# stm8l_resp_v2_0.net
KiCad netlist of a schematic drawn in Altium Designer
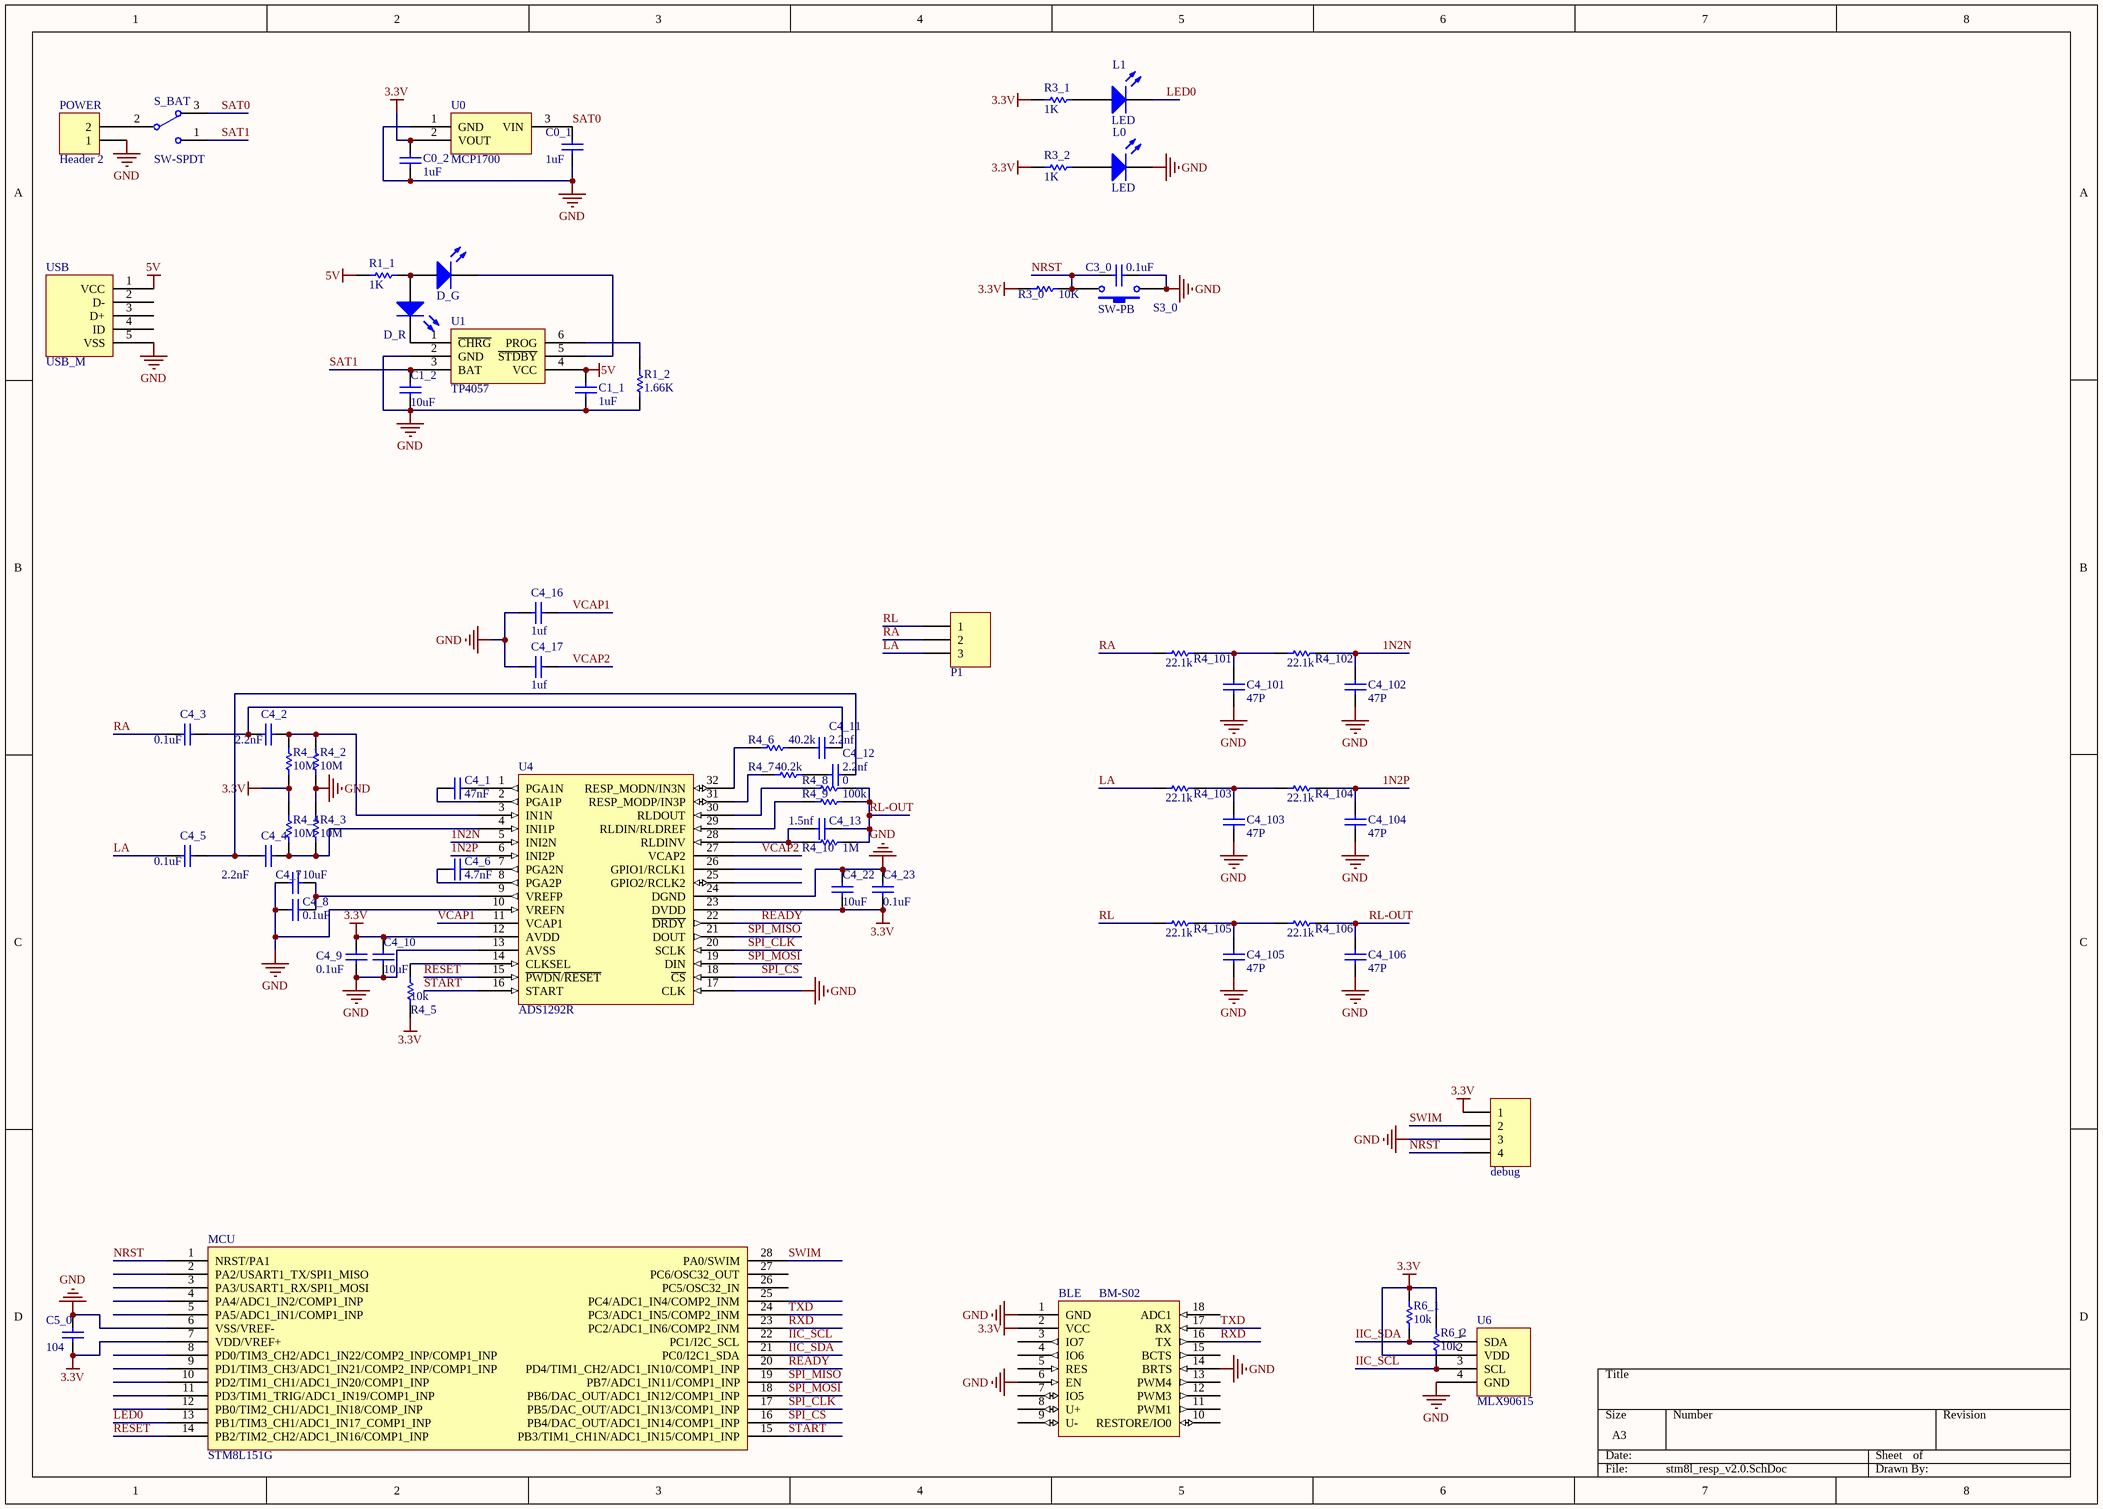
[diagram p0: stm8l_resp_v2.0.SchDoc]

(export (version "E")
  (design (tool "Eeschema 10.0.6"))
  (components
    (comp (ref "BLE")
      (value "BM-S02")
      (footprint "BM-S02")
      (description "蓝牙4.0模块")
      (libsource (lib "Devin_Lib") (part "BM-S02"))
    )
    (comp (ref "C0_1")
      (value "1uF")
      (footprint "C-RAD-0603")
      (description "无极性电容")
      (fields (field (name "Comment") "Cap") (field (name "PUBLISHER") "Altium Limited"))
      (libsource (lib "Devin_Lib") (part "Cap"))
    )
    (comp (ref "C0_2")
      (value "1uF")
      (footprint "C-RAD-0603")
      (description "无极性电容")
      (fields (field (name "Comment") "Cap") (field (name "PUBLISHER") "Altium Limited"))
      (libsource (lib "Devin_Lib") (part "Cap"))
    )
    (comp (ref "C1_1")
      (value "1uF")
      (footprint "C-RAD-0603")
      (description "无极性电容")
      (fields (field (name "Comment") "Cap") (field (name "PUBLISHER") "Altium Limited"))
      (libsource (lib "Devin_Lib") (part "Cap"))
    )
    (comp (ref "C1_2")
      (value "10uF")
      (footprint "C-RAD-0603")
      (description "无极性电容")
      (fields (field (name "Comment") "Cap") (field (name "PUBLISHER") "Altium Limited"))
      (libsource (lib "Schlib1") (part "Cap"))
    )
    (comp (ref "C3_0")
      (value "0.1uF")
      (footprint "C-RAD-0603")
      (description "无极性电容")
      (fields (field (name "Comment") "Cap") (field (name "PUBLISHER") "Altium Limited"))
      (libsource (lib "Fszhang") (part "Cap"))
    )
    (comp (ref "C4_1")
      (value "47nF")
      (footprint "C-RAD-0603")
      (description "无极性电容")
      (fields (field (name "Comment") "Cap") (field (name "PUBLISHER") "Altium Limited"))
      (libsource (lib "Schlib1") (part "Cap"))
    )
    (comp (ref "C4_2")
      (value "2.2nF")
      (footprint "C-RAD-0603")
      (description "无极性电容")
      (fields (field (name "Comment") "Cap") (field (name "PUBLISHER") "Altium Limited"))
      (libsource (lib "Schlib1") (part "Cap"))
    )
    (comp (ref "C4_3")
      (value "0.1uF")
      (footprint "C-RAD-0603")
      (description "无极性电容")
      (fields (field (name "Comment") "Cap") (field (name "PUBLISHER") "Altium Limited"))
      (libsource (lib "Schlib1") (part "Cap"))
    )
    (comp (ref "C4_4")
      (value "2.2nF")
      (footprint "C-RAD-0603")
      (description "无极性电容")
      (fields (field (name "Comment") "Cap") (field (name "PUBLISHER") "Altium Limited"))
      (libsource (lib "Schlib1") (part "Cap"))
    )
    (comp (ref "C4_5")
      (value "0.1uF")
      (footprint "C-RAD-0603")
      (description "无极性电容")
      (fields (field (name "Comment") "Cap") (field (name "PUBLISHER") "Altium Limited"))
      (libsource (lib "Schlib1") (part "Cap"))
    )
    (comp (ref "C4_6")
      (value "4.7nF")
      (footprint "C-RAD-0603")
      (description "无极性电容")
      (fields (field (name "Comment") "Cap") (field (name "PUBLISHER") "Altium Limited"))
      (libsource (lib "Schlib1") (part "Cap"))
    )
    (comp (ref "C4_7")
      (value "10uF")
      (footprint "C-RAD-0603")
      (description "无极性电容")
      (fields (field (name "Comment") "Cap") (field (name "PUBLISHER") "Altium Limited"))
      (libsource (lib "Schlib1") (part "Cap"))
    )
    (comp (ref "C4_8")
      (value "0.1uF")
      (footprint "C-RAD-0603")
      (description "无极性电容")
      (fields (field (name "Comment") "Cap") (field (name "PUBLISHER") "Altium Limited"))
      (libsource (lib "Schlib1") (part "Cap"))
    )
    (comp (ref "C4_9")
      (value "0.1uF")
      (footprint "C-RAD-0603")
      (description "无极性电容")
      (fields (field (name "Comment") "Cap") (field (name "PUBLISHER") "Altium Limited"))
      (libsource (lib "Schlib1") (part "Cap"))
    )
    (comp (ref "C4_10")
      (value "10uF")
      (footprint "C-RAD-0603")
      (description "无极性电容")
      (fields (field (name "Comment") "Cap") (field (name "PUBLISHER") "Altium Limited"))
      (libsource (lib "Schlib1") (part "Cap"))
    )
    (comp (ref "C4_11")
      (value "2.2nf")
      (footprint "C-RAD-0603")
      (description "无极性电容")
      (fields (field (name "Comment") "Cap") (field (name "PUBLISHER") "Altium Limited"))
      (libsource (lib "Schlib1") (part "Cap"))
    )
    (comp (ref "C4_12")
      (value "2.2nf")
      (footprint "C-RAD-0603")
      (description "无极性电容")
      (fields (field (name "Comment") "Cap") (field (name "PUBLISHER") "Altium Limited"))
      (libsource (lib "Schlib1") (part "Cap"))
    )
    (comp (ref "C4_13")
      (value "1.5nf")
      (footprint "C-RAD-0603")
      (description "无极性电容")
      (fields (field (name "Comment") "Cap") (field (name "PUBLISHER") "Altium Limited"))
      (libsource (lib "Schlib1") (part "Cap"))
    )
    (comp (ref "C4_16")
      (value "1uf")
      (footprint "C-RAD-0603")
      (description "无极性电容")
      (fields (field (name "Comment") "Cap") (field (name "PUBLISHER") "Altium Limited"))
      (libsource (lib "Schlib1") (part "Cap"))
    )
    (comp (ref "C4_17")
      (value "1uf")
      (footprint "C-RAD-0603")
      (description "无极性电容")
      (fields (field (name "Comment") "Cap") (field (name "PUBLISHER") "Altium Limited"))
      (libsource (lib "Schlib1") (part "Cap"))
    )
    (comp (ref "C4_22")
      (value "10uF")
      (footprint "C-RAD-0603")
      (description "无极性电容")
      (fields (field (name "Comment") "Cap") (field (name "PUBLISHER") "Altium Limited"))
      (libsource (lib "Schlib1") (part "Cap"))
    )
    (comp (ref "C4_23")
      (value "0.1uF")
      (footprint "C-RAD-0603")
      (description "无极性电容")
      (fields (field (name "Comment") "Cap") (field (name "PUBLISHER") "Altium Limited"))
      (libsource (lib "Schlib1") (part "Cap"))
    )
    (comp (ref "C4_101")
      (value "47P")
      (footprint "C-RAD-0603")
      (description "无极性电容")
      (fields (field (name "Comment") "Cap") (field (name "PUBLISHER") "Altium Limited"))
      (libsource (lib "Schlib1") (part "Cap"))
    )
    (comp (ref "C4_102")
      (value "47P")
      (footprint "C-RAD-0603")
      (description "无极性电容")
      (fields (field (name "Comment") "Cap") (field (name "PUBLISHER") "Altium Limited"))
      (libsource (lib "Schlib1") (part "Cap"))
    )
    (comp (ref "C4_103")
      (value "47P")
      (footprint "C-RAD-0603")
      (description "无极性电容")
      (fields (field (name "Comment") "Cap") (field (name "PUBLISHER") "Altium Limited"))
      (libsource (lib "Schlib1") (part "Cap"))
    )
    (comp (ref "C4_104")
      (value "47P")
      (footprint "C-RAD-0603")
      (description "无极性电容")
      (fields (field (name "Comment") "Cap") (field (name "PUBLISHER") "Altium Limited"))
      (libsource (lib "Schlib1") (part "Cap"))
    )
    (comp (ref "C4_105")
      (value "47P")
      (footprint "C-RAD-0603")
      (description "无极性电容")
      (fields (field (name "Comment") "Cap") (field (name "PUBLISHER") "Altium Limited"))
      (libsource (lib "Schlib1") (part "Cap"))
    )
    (comp (ref "C4_106")
      (value "47P")
      (footprint "C-RAD-0603")
      (description "无极性电容")
      (fields (field (name "Comment") "Cap") (field (name "PUBLISHER") "Altium Limited"))
      (libsource (lib "Schlib1") (part "Cap"))
    )
    (comp (ref "C5_0")
      (value "104")
      (footprint "C-RAD-0603")
      (description "无极性电容")
      (fields (field (name "Comment") "Cap") (field (name "PUBLISHER") "Altium Limited"))
      (libsource (lib "Devin_Lib") (part "Cap"))
    )
    (comp (ref "debug")
      (value "Header 4")
      (footprint "HDR4X1_A")
      (description "接插件")
      (fields (field (name "PUBLISHER") "Altium Limited"))
      (libsource (lib "Devin_Lib") (part "Header 4"))
    )
    (comp (ref "D_G")
      (value "LED0")
      (footprint "0603-LED")
      (description "发光二极管")
      (fields (field (name "PUBLISHER") "Altium Limited"))
      (libsource (lib "Devin_Lib") (part "LED0"))
    )
    (comp (ref "D_R")
      (value "LED0")
      (footprint "0603-LED")
      (description "发光二极管")
      (fields (field (name "PUBLISHER") "Altium Limited"))
      (libsource (lib "Devin_Lib") (part "LED0"))
    )
    (comp (ref "L0") (value "LED") (footprint "0603-LED") (libsource (lib "插针") (part "LED")))
    (comp (ref "L1") (value "LED") (footprint "0603-LED") (libsource (lib "插针") (part "LED")))
    (comp (ref "MCU")
      (value "STM8L151G")
      (footprint "STM8L-QFN28")
      (description "STM8L单片机28引脚")
      (libsource (lib "Devin_Lib") (part "STM8L151G"))
    )
    (comp (ref "P1")
      (value "Header 3")
      (footprint "HDR3X1_A")
      (description "接插件")
      (fields (field (name "PUBLISHER") "Altium Limited"))
      (libsource (lib "Schlib1") (part "Header 3"))
    )
    (comp (ref "POWER")
      (value "Header 2")
      (footprint "HDR1X2")
      (description "Header, 2-Pin")
      (fields (field (name "PUBLISHER") "Altium Limited"))
      (libsource (lib "Miscellaneous Connectors") (part "Header 2"))
    )
    (comp (ref "R1_1")
      (value "1K")
      (footprint "0603-1")
      (description "贴片电阻")
      (fields (field (name "Comment") "Res1") (field (name "PUBLISHER") "Altium Limited"))
      (libsource (lib "Devin_Lib") (part "Res1"))
    )
    (comp (ref "R1_2")
      (value "1.66K")
      (footprint "0603-1")
      (description "贴片电阻")
      (fields (field (name "Comment") "Res1") (field (name "PUBLISHER") "Altium Limited"))
      (libsource (lib "Devin_Lib") (part "Res1"))
    )
    (comp (ref "R3_0")
      (value "10K")
      (footprint "0603-1")
      (description "贴片电阻")
      (fields (field (name "Comment") "Res1") (field (name "PUBLISHER") "Altium Limited"))
      (libsource (lib "Devin_Lib") (part "Res1"))
    )
    (comp (ref "R3_1")
      (value "1K")
      (footprint "0603-1")
      (description "贴片电阻")
      (fields (field (name "Comment") "Res1") (field (name "PUBLISHER") "Altium Limited"))
      (libsource (lib "Devin_Lib") (part "Res1"))
    )
    (comp (ref "R3_2")
      (value "1K")
      (footprint "0603-1")
      (description "贴片电阻")
      (fields (field (name "Comment") "Res1") (field (name "PUBLISHER") "Altium Limited"))
      (libsource (lib "Devin_Lib") (part "Res1"))
    )
    (comp (ref "R4_1")
      (value "10M")
      (footprint "0603-1")
      (description "贴片电阻")
      (fields (field (name "Comment") "Res1") (field (name "PUBLISHER") "Altium Limited"))
      (libsource (lib "Schlib1") (part "Res1"))
    )
    (comp (ref "R4_2")
      (value "10M")
      (footprint "0603-1")
      (description "贴片电阻")
      (fields (field (name "Comment") "Res1") (field (name "PUBLISHER") "Altium Limited"))
      (libsource (lib "Schlib1") (part "Res1"))
    )
    (comp (ref "R4_3")
      (value "10M")
      (footprint "0603-1")
      (description "贴片电阻")
      (fields (field (name "Comment") "Res1") (field (name "PUBLISHER") "Altium Limited"))
      (libsource (lib "Schlib1") (part "Res1"))
    )
    (comp (ref "R4_4")
      (value "10M")
      (footprint "0603-1")
      (description "贴片电阻")
      (fields (field (name "Comment") "Res1") (field (name "PUBLISHER") "Altium Limited"))
      (libsource (lib "Schlib1") (part "Res1"))
    )
    (comp (ref "R4_5")
      (value "10k")
      (footprint "0603-1")
      (description "贴片电阻")
      (fields (field (name "Comment") "Res1") (field (name "PUBLISHER") "Altium Limited"))
      (libsource (lib "Schlib1") (part "Res1"))
    )
    (comp (ref "R4_6")
      (value "40.2k")
      (footprint "0603-1")
      (description "贴片电阻")
      (fields (field (name "Comment") "Res1") (field (name "PUBLISHER") "Altium Limited"))
      (libsource (lib "Schlib1") (part "Res1"))
    )
    (comp (ref "R4_7")
      (value "40.2k")
      (footprint "0603-1")
      (description "贴片电阻")
      (fields (field (name "Comment") "Res1") (field (name "PUBLISHER") "Altium Limited"))
      (libsource (lib "Schlib1") (part "Res1"))
    )
    (comp (ref "R4_8")
      (value "0")
      (footprint "0603-1")
      (description "贴片电阻")
      (fields (field (name "Comment") "Res1") (field (name "PUBLISHER") "Altium Limited"))
      (libsource (lib "Schlib1") (part "Res1"))
    )
    (comp (ref "R4_9")
      (value "100k")
      (footprint "0603-1")
      (description "贴片电阻")
      (fields (field (name "Comment") "Res1") (field (name "PUBLISHER") "Altium Limited"))
      (libsource (lib "Schlib1") (part "Res1"))
    )
    (comp (ref "R4_10")
      (value "1M")
      (footprint "0603-1")
      (description "贴片电阻")
      (fields (field (name "Comment") "Res1") (field (name "PUBLISHER") "Altium Limited"))
      (libsource (lib "Schlib1") (part "Res1"))
    )
    (comp (ref "R4_101")
      (value "22.1k")
      (footprint "0603-1")
      (description "贴片电阻")
      (fields (field (name "Comment") "Res1") (field (name "PUBLISHER") "Altium Limited"))
      (libsource (lib "Schlib1") (part "Res1"))
    )
    (comp (ref "R4_102")
      (value "22.1k")
      (footprint "0603-1")
      (description "贴片电阻")
      (fields (field (name "Comment") "Res1") (field (name "PUBLISHER") "Altium Limited"))
      (libsource (lib "Schlib1") (part "Res1"))
    )
    (comp (ref "R4_103")
      (value "22.1k")
      (footprint "0603-1")
      (description "贴片电阻")
      (fields (field (name "Comment") "Res1") (field (name "PUBLISHER") "Altium Limited"))
      (libsource (lib "Schlib1") (part "Res1"))
    )
    (comp (ref "R4_104")
      (value "22.1k")
      (footprint "0603-1")
      (description "贴片电阻")
      (fields (field (name "Comment") "Res1") (field (name "PUBLISHER") "Altium Limited"))
      (libsource (lib "Schlib1") (part "Res1"))
    )
    (comp (ref "R4_105")
      (value "22.1k")
      (footprint "0603-1")
      (description "贴片电阻")
      (fields (field (name "Comment") "Res1") (field (name "PUBLISHER") "Altium Limited"))
      (libsource (lib "Schlib1") (part "Res1"))
    )
    (comp (ref "R4_106")
      (value "22.1k")
      (footprint "0603-1")
      (description "贴片电阻")
      (fields (field (name "Comment") "Res1") (field (name "PUBLISHER") "Altium Limited"))
      (libsource (lib "Schlib1") (part "Res1"))
    )
    (comp (ref "R6_1")
      (value "10k")
      (footprint "0603-1")
      (description "贴片电阻")
      (fields (field (name "Comment") "Res1") (field (name "PUBLISHER") "Altium Limited"))
      (libsource (lib "Schlib1") (part "Res1"))
    )
    (comp (ref "R6_2")
      (value "10k")
      (footprint "0603-1")
      (description "贴片电阻")
      (fields (field (name "Comment") "Res1") (field (name "PUBLISHER") "Altium Limited"))
      (libsource (lib "Schlib1") (part "Res1"))
    )
    (comp (ref "S3_0")
      (value "SW-PB")
      (footprint "SW_PB2_2*4")
      (description "微动开关")
      (fields (field (name "PUBLISHER") "Altium Limited"))
      (libsource (lib "Devin_Lib") (part "SW-PB"))
    )
    (comp (ref "S_BAT")
      (value "SW-SPDT")
      (footprint "SWITCH_1P2T")
      (description "开关")
      (fields (field (name "PUBLISHER") "Altium Limited"))
      (libsource (lib "Devin_Lib") (part "SW-SPDT"))
    )
    (comp (ref "U0")
      (value "MCP1700")
      (footprint "SOT-23")
      (description "微型稳压芯片")
      (libsource (lib "Devin_Lib") (part "MCP1700"))
    )
    (comp (ref "U1")
      (value "TP4057")
      (footprint "TP4057")
      (description "锂电池充电管理")
      (libsource (lib "Devin_Lib") (part "TP4057"))
    )
    (comp (ref "U4")
      (value "ADS1292R")
      (footprint "ADS1292R-QFN-32")
      (description "集成呼吸阻抗 ECG 前端")
      (libsource (lib "Schlib1") (part "ADS1292R"))
    )
    (comp (ref "U6")
      (value "MLX90615")
      (footprint "MLX90615-2")
      (description "红外体温传感器")
      (libsource (lib "Devin_Lib") (part "MLX90615"))
    )
    (comp (ref "USB")
      (value "USB_M")
      (footprint "USB_MICRO")
      (description "MicroUSB接口")
      (libsource (lib "Devin_Lib") (part "USB_M"))
    )
  )
  (nets
    (net (code "1") (name "/1N2N") (class "Default")
      (node (ref "C4_102") (pin "1") (pinfunction "1_1") (pintype "passive"))
      (node (ref "R4_102") (pin "2") (pinfunction "2_2") (pintype "passive"))
      (node (ref "U4") (pin "5") (pinfunction "INI2N_5") (pintype "input"))
    )
    (net (code "2") (name "/1N2P") (class "Default")
      (node (ref "C4_104") (pin "1") (pinfunction "1_1") (pintype "passive"))
      (node (ref "R4_104") (pin "2") (pinfunction "2_2") (pintype "passive"))
      (node (ref "U4") (pin "6") (pinfunction "INI2P_6") (pintype "input"))
    )
    (net (code "3") (name "/IIC_SCL") (class "Default")
      (node (ref "MCU") (pin "22") (pinfunction "PC1/I2C_SCL_22") (pintype "passive"))
      (node (ref "R6_2") (pin "1") (pinfunction "1_1") (pintype "passive"))
      (node (ref "U6") (pin "3") (pinfunction "SCL_3") (pintype "passive"))
    )
    (net (code "4") (name "/IIC_SDA") (class "Default")
      (node (ref "MCU") (pin "21") (pinfunction "PC0/I2C1_SDA_21") (pintype "passive"))
      (node (ref "R6_1") (pin "1") (pinfunction "1_1") (pintype "passive"))
      (node (ref "U6") (pin "1") (pinfunction "SDA_1") (pintype "passive"))
    )
    (net (code "5") (name "/LA") (class "Default")
      (node (ref "C4_5") (pin "1") (pinfunction "1_1") (pintype "passive"))
      (node (ref "P1") (pin "3") (pinfunction "3_3") (pintype "passive"))
      (node (ref "R4_103") (pin "1") (pinfunction "1_1") (pintype "passive"))
    )
    (net (code "6") (name "/LED0") (class "Default")
      (node (ref "L1") (pin "2") (pinfunction "K_2") (pintype "passive"))
      (node (ref "MCU") (pin "13") (pinfunction "PB1/TIM3_CH1/ADC1_IN17_COMP1_INP_13") (pintype "passive"))
    )
    (net (code "7") (name "/NRST") (class "Default")
      (node (ref "C3_0") (pin "2") (pinfunction "2_2") (pintype "passive"))
      (node (ref "MCU") (pin "1") (pinfunction "NRST/PA1_1") (pintype "passive"))
      (node (ref "R3_0") (pin "2") (pinfunction "2_2") (pintype "passive"))
      (node (ref "S3_0") (pin "2") (pinfunction "2_2") (pintype "passive"))
      (node (ref "debug") (pin "4") (pinfunction "4_4") (pintype "passive"))
    )
    (net (code "8") (name "/RA") (class "Default")
      (node (ref "C4_3") (pin "1") (pinfunction "1_1") (pintype "passive"))
      (node (ref "P1") (pin "2") (pinfunction "2_2") (pintype "passive"))
      (node (ref "R4_101") (pin "1") (pinfunction "1_1") (pintype "passive"))
    )
    (net (code "9") (name "/READY") (class "Default")
      (node (ref "MCU") (pin "20") (pinfunction "PD4/TIM1_CH2/ADC1_IN10/COMP1_INP_20") (pintype "passive"))
      (node (ref "U4") (pin "22") (pinfunction "~{DRDY}_22") (pintype "output"))
    )
    (net (code "10") (name "/RESET") (class "Default")
      (node (ref "MCU") (pin "14") (pinfunction "PB2/TIM2_CH2/ADC1_IN16/COMP1_INP_14") (pintype "passive"))
      (node (ref "U4") (pin "15") (pinfunction "~{PWDN}/~{RESET}_15") (pintype "input"))
    )
    (net (code "11") (name "/RL") (class "Default")
      (node (ref "P1") (pin "1") (pinfunction "1_1") (pintype "passive"))
      (node (ref "R4_105") (pin "1") (pinfunction "1_1") (pintype "passive"))
    )
    (net (code "12") (name "/RL-OUT") (class "Default")
      (node (ref "C4_106") (pin "1") (pinfunction "1_1") (pintype "passive"))
      (node (ref "C4_13") (pin "1") (pinfunction "1_1") (pintype "passive"))
      (node (ref "R4_10") (pin "2") (pinfunction "2_2") (pintype "passive"))
      (node (ref "R4_106") (pin "2") (pinfunction "2_2") (pintype "passive"))
      (node (ref "R4_8") (pin "1") (pinfunction "1_1") (pintype "passive"))
      (node (ref "R4_9") (pin "2") (pinfunction "2_2") (pintype "passive"))
    )
    (net (code "13") (name "/RXD") (class "Default")
      (node (ref "BLE") (pin "16") (pinfunction "TX_16") (pintype "output"))
      (node (ref "MCU") (pin "23") (pinfunction "PC2/ADC1_IN6/COMP2_INM_23") (pintype "passive"))
    )
    (net (code "14") (name "/SAT0") (class "Default")
      (node (ref "C0_1") (pin "2") (pinfunction "2_2") (pintype "passive"))
      (node (ref "S_BAT") (pin "3") (pinfunction "3_3") (pintype "passive"))
      (node (ref "U0") (pin "3") (pinfunction "VIN_3") (pintype "passive"))
    )
    (net (code "15") (name "/SAT1") (class "Default")
      (node (ref "C1_2") (pin "1") (pinfunction "1_1") (pintype "passive"))
      (node (ref "S_BAT") (pin "1") (pinfunction "1_1") (pintype "passive"))
      (node (ref "U1") (pin "3") (pinfunction "BAT_3") (pintype "passive"))
    )
    (net (code "16") (name "/SPI_CLK") (class "Default")
      (node (ref "MCU") (pin "17") (pinfunction "PB5/DAC_OUT/ADC1_IN13/COMP1_INP_17") (pintype "passive"))
      (node (ref "U4") (pin "20") (pinfunction "SCLK_20") (pintype "input"))
    )
    (net (code "17") (name "/SPI_CS") (class "Default")
      (node (ref "MCU") (pin "16") (pinfunction "PB4/DAC_OUT/ADC1_IN14/COMP1_INP_16") (pintype "passive"))
      (node (ref "U4") (pin "18") (pinfunction "~{CS}_18") (pintype "input"))
    )
    (net (code "18") (name "/SPI_MISO") (class "Default")
      (node (ref "MCU") (pin "19") (pinfunction "PB7/ADC1_IN11/COMP1_INP_19") (pintype "passive"))
      (node (ref "U4") (pin "21") (pinfunction "DOUT_21") (pintype "output"))
    )
    (net (code "19") (name "/SPI_MOSI") (class "Default")
      (node (ref "MCU") (pin "18") (pinfunction "PB6/DAC_OUT/ADC1_IN12/COMP1_INP_18") (pintype "passive"))
      (node (ref "U4") (pin "19") (pinfunction "DIN_19") (pintype "input"))
    )
    (net (code "20") (name "/START") (class "Default")
      (node (ref "MCU") (pin "15") (pinfunction "PB3/TIM1_CH1N/ADC1_IN15/COMP1_INP_15") (pintype "passive"))
      (node (ref "U4") (pin "16") (pinfunction "START_16") (pintype "input"))
    )
    (net (code "21") (name "/SWIM") (class "Default")
      (node (ref "MCU") (pin "28") (pinfunction "PA0/SWIM_28") (pintype "passive"))
      (node (ref "debug") (pin "2") (pinfunction "2_2") (pintype "passive"))
    )
    (net (code "22") (name "/TXD") (class "Default")
      (node (ref "BLE") (pin "17") (pinfunction "RX_17") (pintype "input"))
      (node (ref "MCU") (pin "24") (pinfunction "PC3/ADC1_IN5/COMP2_INM_24") (pintype "passive"))
    )
    (net (code "23") (name "/VCAP1") (class "Default")
      (node (ref "C4_16") (pin "1") (pinfunction "1_1") (pintype "passive"))
      (node (ref "U4") (pin "11") (pinfunction "VCAP1_11") (pintype "passive"))
    )
    (net (code "24") (name "/VCAP2") (class "Default")
      (node (ref "C4_17") (pin "1") (pinfunction "1_1") (pintype "passive"))
      (node (ref "U4") (pin "27") (pinfunction "VCAP2_27") (pintype "passive"))
    )
    (net (code "25") (name "3.3V") (class "Default")
      (node (ref "BLE") (pin "2") (pinfunction "VCC_2") (pintype "passive"))
      (node (ref "C0_2") (pin "2") (pinfunction "2_2") (pintype "passive"))
      (node (ref "C4_10") (pin "1") (pinfunction "1_1") (pintype "passive"))
      (node (ref "C4_22") (pin "2") (pinfunction "2_2") (pintype "passive"))
      (node (ref "C4_23") (pin "2") (pinfunction "2_2") (pintype "passive"))
      (node (ref "C4_9") (pin "1") (pinfunction "1_1") (pintype "passive"))
      (node (ref "C5_0") (pin "1") (pinfunction "1_1") (pintype "passive"))
      (node (ref "MCU") (pin "7") (pinfunction "VDD/VREF+_7") (pintype "passive"))
      (node (ref "R3_0") (pin "1") (pinfunction "1_1") (pintype "passive"))
      (node (ref "R3_1") (pin "1") (pinfunction "1_1") (pintype "passive"))
      (node (ref "R3_2") (pin "1") (pinfunction "1_1") (pintype "passive"))
      (node (ref "R4_1") (pin "1") (pinfunction "1_1") (pintype "passive"))
      (node (ref "R4_4") (pin "2") (pinfunction "2_2") (pintype "passive"))
      (node (ref "R4_5") (pin "1") (pinfunction "1_1") (pintype "passive"))
      (node (ref "R6_1") (pin "2") (pinfunction "2_2") (pintype "passive"))
      (node (ref "R6_2") (pin "2") (pinfunction "2_2") (pintype "passive"))
      (node (ref "U0") (pin "2") (pinfunction "VOUT_2") (pintype "passive"))
      (node (ref "U4") (pin "12") (pinfunction "AVDD_12") (pintype "passive"))
      (node (ref "U4") (pin "23") (pinfunction "DVDD_23") (pintype "passive"))
      (node (ref "U6") (pin "2") (pinfunction "VDD_2") (pintype "passive"))
      (node (ref "debug") (pin "1") (pinfunction "1_1") (pintype "passive"))
    )
    (net (code "26") (name "5V") (class "Default")
      (node (ref "C1_1") (pin "2") (pinfunction "2_2") (pintype "passive"))
      (node (ref "R1_1") (pin "2") (pinfunction "2_2") (pintype "passive"))
      (node (ref "U1") (pin "4") (pinfunction "VCC_4") (pintype "passive"))
      (node (ref "USB") (pin "1") (pinfunction "VCC_1") (pintype "passive"))
    )
    (net (code "27") (name "GND") (class "Default")
      (node (ref "BLE") (pin "1") (pinfunction "GND_1") (pintype "passive"))
      (node (ref "BLE") (pin "14") (pinfunction "BRTS_14") (pintype "input"))
      (node (ref "BLE") (pin "6") (pinfunction "EN_6") (pintype "input"))
      (node (ref "C0_1") (pin "1") (pinfunction "1_1") (pintype "passive"))
      (node (ref "C0_2") (pin "1") (pinfunction "1_1") (pintype "passive"))
      (node (ref "C1_1") (pin "1") (pinfunction "1_1") (pintype "passive"))
      (node (ref "C1_2") (pin "2") (pinfunction "2_2") (pintype "passive"))
      (node (ref "C3_0") (pin "1") (pinfunction "1_1") (pintype "passive"))
      (node (ref "C4_10") (pin "2") (pinfunction "2_2") (pintype "passive"))
      (node (ref "C4_101") (pin "2") (pinfunction "2_2") (pintype "passive"))
      (node (ref "C4_102") (pin "2") (pinfunction "2_2") (pintype "passive"))
      (node (ref "C4_103") (pin "2") (pinfunction "2_2") (pintype "passive"))
      (node (ref "C4_104") (pin "2") (pinfunction "2_2") (pintype "passive"))
      (node (ref "C4_105") (pin "2") (pinfunction "2_2") (pintype "passive"))
      (node (ref "C4_106") (pin "2") (pinfunction "2_2") (pintype "passive"))
      (node (ref "C4_16") (pin "2") (pinfunction "2_2") (pintype "passive"))
      (node (ref "C4_17") (pin "2") (pinfunction "2_2") (pintype "passive"))
      (node (ref "C4_22") (pin "1") (pinfunction "1_1") (pintype "passive"))
      (node (ref "C4_23") (pin "1") (pinfunction "1_1") (pintype "passive"))
      (node (ref "C4_7") (pin "1") (pinfunction "1_1") (pintype "passive"))
      (node (ref "C4_8") (pin "2") (pinfunction "2_2") (pintype "passive"))
      (node (ref "C4_9") (pin "2") (pinfunction "2_2") (pintype "passive"))
      (node (ref "C5_0") (pin "2") (pinfunction "2_2") (pintype "passive"))
      (node (ref "L0") (pin "2") (pinfunction "K_2") (pintype "passive"))
      (node (ref "MCU") (pin "6") (pinfunction "VSS/VREF-_6") (pintype "passive"))
      (node (ref "POWER") (pin "1") (pinfunction "1_1") (pintype "passive"))
      (node (ref "R1_2") (pin "2") (pinfunction "2_2") (pintype "passive"))
      (node (ref "R4_2") (pin "1") (pinfunction "1_1") (pintype "passive"))
      (node (ref "R4_3") (pin "2") (pinfunction "2_2") (pintype "passive"))
      (node (ref "S3_0") (pin "1") (pinfunction "1_1") (pintype "passive"))
      (node (ref "U0") (pin "1") (pinfunction "GND_1") (pintype "passive"))
      (node (ref "U1") (pin "2") (pinfunction "GND_2") (pintype "passive"))
      (node (ref "U4") (pin "10") (pinfunction "VREFN_10") (pintype "input"))
      (node (ref "U4") (pin "13") (pinfunction "AVSS_13") (pintype "passive"))
      (node (ref "U4") (pin "17") (pinfunction "CLK_17") (pintype "input"))
      (node (ref "U4") (pin "24") (pinfunction "DGND_24") (pintype "passive"))
      (node (ref "U6") (pin "4") (pinfunction "GND_4") (pintype "passive"))
      (node (ref "USB") (pin "5") (pinfunction "VSS_5") (pintype "passive"))
      (node (ref "debug") (pin "3") (pinfunction "3_3") (pintype "passive"))
    )
    (net (code "28") (name "Net-(C4_11-Pad1)") (class "Default")
      (node (ref "C4_11") (pin "1") (pinfunction "1_1") (pintype "passive"))
      (node (ref "C4_2") (pin "1") (pinfunction "1_1") (pintype "passive"))
      (node (ref "C4_3") (pin "2") (pinfunction "2_2") (pintype "passive"))
    )
    (net (code "29") (name "Net-(C4_11-Pad2)") (class "Default")
      (node (ref "C4_11") (pin "2") (pinfunction "2_2") (pintype "passive"))
      (node (ref "R4_6") (pin "2") (pinfunction "2_2") (pintype "passive"))
    )
    (net (code "30") (name "Net-(C4_12-Pad1)") (class "Default")
      (node (ref "C4_12") (pin "1") (pinfunction "1_1") (pintype "passive"))
      (node (ref "C4_4") (pin "1") (pinfunction "1_1") (pintype "passive"))
      (node (ref "C4_5") (pin "2") (pinfunction "2_2") (pintype "passive"))
    )
    (net (code "31") (name "Net-(C4_12-Pad2)") (class "Default")
      (node (ref "C4_12") (pin "2") (pinfunction "2_2") (pintype "passive"))
      (node (ref "R4_7") (pin "1") (pinfunction "1_1") (pintype "passive"))
    )
    (net (code "32") (name "Net-(C4_101-Pad1)") (class "Default")
      (node (ref "C4_101") (pin "1") (pinfunction "1_1") (pintype "passive"))
      (node (ref "R4_101") (pin "2") (pinfunction "2_2") (pintype "passive"))
      (node (ref "R4_102") (pin "1") (pinfunction "1_1") (pintype "passive"))
    )
    (net (code "33") (name "Net-(C4_103-Pad1)") (class "Default")
      (node (ref "C4_103") (pin "1") (pinfunction "1_1") (pintype "passive"))
      (node (ref "R4_103") (pin "2") (pinfunction "2_2") (pintype "passive"))
      (node (ref "R4_104") (pin "1") (pinfunction "1_1") (pintype "passive"))
    )
    (net (code "34") (name "Net-(C4_105-Pad1)") (class "Default")
      (node (ref "C4_105") (pin "1") (pinfunction "1_1") (pintype "passive"))
      (node (ref "R4_105") (pin "2") (pinfunction "2_2") (pintype "passive"))
      (node (ref "R4_106") (pin "1") (pinfunction "1_1") (pintype "passive"))
    )
    (net (code "35") (name "Net-(D_G-A)") (class "Default")
      (node (ref "D_G") (pin "1") (pinfunction "A_1") (pintype "passive"))
      (node (ref "D_R") (pin "1") (pinfunction "A_1") (pintype "passive"))
      (node (ref "R1_1") (pin "1") (pinfunction "1_1") (pintype "passive"))
    )
    (net (code "36") (name "Net-(D_G-K)") (class "Default")
      (node (ref "D_G") (pin "2") (pinfunction "K_2") (pintype "passive"))
      (node (ref "U1") (pin "5") (pinfunction "~{STDBY}_5") (pintype "passive"))
    )
    (net (code "37") (name "Net-(D_R-K)") (class "Default")
      (node (ref "D_R") (pin "2") (pinfunction "K_2") (pintype "passive"))
      (node (ref "U1") (pin "1") (pinfunction "~{CHRG}_1") (pintype "passive"))
    )
    (net (code "38") (name "Net-(L0-A)") (class "Default")
      (node (ref "L0") (pin "1") (pinfunction "A_1") (pintype "passive"))
      (node (ref "R3_2") (pin "2") (pinfunction "2_2") (pintype "passive"))
    )
    (net (code "39") (name "Net-(L1-A)") (class "Default")
      (node (ref "L1") (pin "1") (pinfunction "A_1") (pintype "passive"))
      (node (ref "R3_1") (pin "2") (pinfunction "2_2") (pintype "passive"))
    )
    (net (code "40") (name "Net-(POWER-Pad2)") (class "Default")
      (node (ref "POWER") (pin "2") (pinfunction "2_2") (pintype "passive"))
      (node (ref "S_BAT") (pin "2") (pinfunction "2_2") (pintype "passive"))
    )
    (net (code "41") (name "Net-(U1-PROG)") (class "Default")
      (node (ref "R1_2") (pin "1") (pinfunction "1_1") (pintype "passive"))
      (node (ref "U1") (pin "6") (pinfunction "PROG_6") (pintype "passive"))
    )
    (net (code "42") (name "Net-(U4-CLKSEL)") (class "Default")
      (node (ref "R4_5") (pin "2") (pinfunction "2_2") (pintype "passive"))
      (node (ref "U4") (pin "14") (pinfunction "CLKSEL_14") (pintype "input"))
    )
    (net (code "43") (name "Net-(U4-IN1N)") (class "Default")
      (node (ref "C4_2") (pin "2") (pinfunction "2_2") (pintype "passive"))
      (node (ref "R4_1") (pin "2") (pinfunction "2_2") (pintype "passive"))
      (node (ref "R4_2") (pin "2") (pinfunction "2_2") (pintype "passive"))
      (node (ref "U4") (pin "3") (pinfunction "IN1N_3") (pintype "input"))
    )
    (net (code "44") (name "Net-(U4-INI1P)") (class "Default")
      (node (ref "C4_4") (pin "2") (pinfunction "2_2") (pintype "passive"))
      (node (ref "R4_3") (pin "1") (pinfunction "1_1") (pintype "passive"))
      (node (ref "R4_4") (pin "1") (pinfunction "1_1") (pintype "passive"))
      (node (ref "U4") (pin "4") (pinfunction "INI1P_4") (pintype "input"))
    )
    (net (code "45") (name "Net-(U4-PGA1N)") (class "Default")
      (node (ref "C4_1") (pin "2") (pinfunction "2_2") (pintype "passive"))
      (node (ref "U4") (pin "1") (pinfunction "PGA1N_1") (pintype "output"))
    )
    (net (code "46") (name "Net-(U4-PGA1P)") (class "Default")
      (node (ref "C4_1") (pin "1") (pinfunction "1_1") (pintype "passive"))
      (node (ref "U4") (pin "2") (pinfunction "PGA1P_2") (pintype "output"))
    )
    (net (code "47") (name "Net-(U4-PGA2N)") (class "Default")
      (node (ref "C4_6") (pin "1") (pinfunction "1_1") (pintype "passive"))
      (node (ref "U4") (pin "7") (pinfunction "PGA2N_7") (pintype "output"))
    )
    (net (code "48") (name "Net-(U4-PGA2P)") (class "Default")
      (node (ref "C4_6") (pin "2") (pinfunction "2_2") (pintype "passive"))
      (node (ref "U4") (pin "8") (pinfunction "PGA2P_8") (pintype "output"))
    )
    (net (code "49") (name "Net-(U4-RESP_MODN{slash}IN3N)") (class "Default")
      (node (ref "R4_6") (pin "1") (pinfunction "1_1") (pintype "passive"))
      (node (ref "U4") (pin "32") (pinfunction "RESP_MODN/IN3N_32") (pintype "bidirectional"))
    )
    (net (code "50") (name "Net-(U4-RESP_MODP{slash}IN3P)") (class "Default")
      (node (ref "R4_7") (pin "2") (pinfunction "2_2") (pintype "passive"))
      (node (ref "U4") (pin "31") (pinfunction "RESP_MODP/IN3P_31") (pintype "bidirectional"))
    )
    (net (code "51") (name "Net-(U4-RLDINV)") (class "Default")
      (node (ref "C4_13") (pin "2") (pinfunction "2_2") (pintype "passive"))
      (node (ref "R4_10") (pin "1") (pinfunction "1_1") (pintype "passive"))
      (node (ref "U4") (pin "28") (pinfunction "RLDINV_28") (pintype "input"))
    )
    (net (code "52") (name "Net-(U4-RLDIN{slash}RLDREF)") (class "Default")
      (node (ref "R4_9") (pin "1") (pinfunction "1_1") (pintype "passive"))
      (node (ref "U4") (pin "29") (pinfunction "RLDIN/RLDREF_29") (pintype "input"))
    )
    (net (code "53") (name "Net-(U4-RLDOUT)") (class "Default")
      (node (ref "R4_8") (pin "2") (pinfunction "2_2") (pintype "passive"))
      (node (ref "U4") (pin "30") (pinfunction "RLDOUT_30") (pintype "input"))
    )
    (net (code "54") (name "Net-(U4-VREFP)") (class "Default")
      (node (ref "C4_7") (pin "2") (pinfunction "2_2") (pintype "passive"))
      (node (ref "C4_8") (pin "1") (pinfunction "1_1") (pintype "passive"))
      (node (ref "U4") (pin "9") (pinfunction "VREFP_9") (pintype "output"))
    )
    (net (code "55") (name "unconnected-(BLE-ADC1-Pad18)") (class "Default")
      (node (ref "BLE") (pin "18") (pinfunction "ADC1_18") (pintype "input"))
    )
    (net (code "56") (name "unconnected-(BLE-BCTS-Pad15)") (class "Default")
      (node (ref "BLE") (pin "15") (pinfunction "BCTS_15") (pintype "output"))
    )
    (net (code "57") (name "unconnected-(BLE-IO5-Pad7)") (class "Default")
      (node (ref "BLE") (pin "7") (pinfunction "IO5_7") (pintype "bidirectional"))
    )
    (net (code "58") (name "unconnected-(BLE-IO6-Pad4)") (class "Default")
      (node (ref "BLE") (pin "4") (pinfunction "IO6_4") (pintype "output"))
    )
    (net (code "59") (name "unconnected-(BLE-IO7-Pad3)") (class "Default")
      (node (ref "BLE") (pin "3") (pinfunction "IO7_3") (pintype "output"))
    )
    (net (code "60") (name "unconnected-(BLE-PWM1-Pad11)") (class "Default")
      (node (ref "BLE") (pin "11") (pinfunction "PWM1_11") (pintype "output"))
    )
    (net (code "61") (name "unconnected-(BLE-PWM3-Pad12)") (class "Default")
      (node (ref "BLE") (pin "12") (pinfunction "PWM3_12") (pintype "output"))
    )
    (net (code "62") (name "unconnected-(BLE-PWM4-Pad13)") (class "Default")
      (node (ref "BLE") (pin "13") (pinfunction "PWM4_13") (pintype "output"))
    )
    (net (code "63") (name "unconnected-(BLE-RES-Pad5)") (class "Default")
      (node (ref "BLE") (pin "5") (pinfunction "RES_5") (pintype "input"))
    )
    (net (code "64") (name "unconnected-(BLE-RESTORE{slash}IO0-Pad10)") (class "Default")
      (node (ref "BLE") (pin "10") (pinfunction "RESTORE/IO0_10") (pintype "bidirectional"))
    )
    (net (code "65") (name "unconnected-(BLE-U+-Pad8)") (class "Default")
      (node (ref "BLE") (pin "8") (pinfunction "U+_8") (pintype "bidirectional"))
    )
    (net (code "66") (name "unconnected-(BLE-U--Pad9)") (class "Default")
      (node (ref "BLE") (pin "9") (pinfunction "U-_9") (pintype "bidirectional"))
    )
    (net (code "67") (name "unconnected-(MCU-PA2{slash}USART1_TX{slash}SPI1_MISO-Pad2)") (class "Default")
      (node (ref "MCU") (pin "2") (pinfunction "PA2/USART1_TX/SPI1_MISO_2") (pintype "passive"))
    )
    (net (code "68") (name "unconnected-(MCU-PA3{slash}USART1_RX{slash}SPI1_MOSI-Pad3)") (class "Default")
      (node (ref "MCU") (pin "3") (pinfunction "PA3/USART1_RX/SPI1_MOSI_3") (pintype "passive"))
    )
    (net (code "69") (name "unconnected-(MCU-PA4{slash}ADC1_IN2{slash}COMP1_INP-Pad4)") (class "Default")
      (node (ref "MCU") (pin "4") (pinfunction "PA4/ADC1_IN2/COMP1_INP_4") (pintype "passive"))
    )
    (net (code "70") (name "unconnected-(MCU-PA5{slash}ADC1_IN1{slash}COMP1_INP-Pad5)") (class "Default")
      (node (ref "MCU") (pin "5") (pinfunction "PA5/ADC1_IN1/COMP1_INP_5") (pintype "passive"))
    )
    (net (code "71") (name "unconnected-(MCU-PB0{slash}TIM2_CH1{slash}ADC1_IN18{slash}COMP_INP-Pad12)") (class "Default")
      (node (ref "MCU") (pin "12") (pinfunction "PB0/TIM2_CH1/ADC1_IN18/COMP_INP_12") (pintype "passive"))
    )
    (net (code "72") (name "unconnected-(MCU-PC4{slash}ADC1_IN4{slash}COMP2_INM-Pad25)") (class "Default")
      (node (ref "MCU") (pin "25") (pinfunction "PC4/ADC1_IN4/COMP2_INM_25") (pintype "passive"))
    )
    (net (code "73") (name "unconnected-(MCU-PC5{slash}OSC32_IN-Pad26)") (class "Default")
      (node (ref "MCU") (pin "26") (pinfunction "PC5/OSC32_IN_26") (pintype "passive"))
    )
    (net (code "74") (name "unconnected-(MCU-PC6{slash}OSC32_OUT-Pad27)") (class "Default")
      (node (ref "MCU") (pin "27") (pinfunction "PC6/OSC32_OUT_27") (pintype "passive"))
    )
    (net (code "75") (name "unconnected-(MCU-PD0{slash}TIM3_CH2{slash}ADC1_IN22{slash}COMP2_INP{slash}COMP1_INP-Pad8)") (class "Default")
      (node (ref "MCU") (pin "8") (pinfunction "PD0/TIM3_CH2/ADC1_IN22/COMP2_INP/COMP1_INP_8") (pintype "passive"))
    )
    (net (code "76") (name "unconnected-(MCU-PD1{slash}TIM3_CH3{slash}ADC1_IN21{slash}COMP2_INP{slash}COMP1_INP-Pad9)") (class "Default")
      (node (ref "MCU") (pin "9") (pinfunction "PD1/TIM3_CH3/ADC1_IN21/COMP2_INP/COMP1_INP_9") (pintype "passive"))
    )
    (net (code "77") (name "unconnected-(MCU-PD2{slash}TIM1_CH1{slash}ADC1_IN20{slash}COMP1_INP-Pad10)") (class "Default")
      (node (ref "MCU") (pin "10") (pinfunction "PD2/TIM1_CH1/ADC1_IN20/COMP1_INP_10") (pintype "passive"))
    )
    (net (code "78") (name "unconnected-(MCU-PD3{slash}TIM1_TRIG{slash}ADC1_IN19{slash}COMP1_INP-Pad11)") (class "Default")
      (node (ref "MCU") (pin "11") (pinfunction "PD3/TIM1_TRIG/ADC1_IN19/COMP1_INP_11") (pintype "passive"))
    )
    (net (code "79") (name "unconnected-(U4-GPIO1{slash}RCLK1-Pad26)") (class "Default")
      (node (ref "U4") (pin "26") (pinfunction "GPIO1/RCLK1_26") (pintype "passive"))
    )
    (net (code "80") (name "unconnected-(U4-GPIO2{slash}RCLK2-Pad25)") (class "Default")
      (node (ref "U4") (pin "25") (pinfunction "GPIO2/RCLK2_25") (pintype "bidirectional"))
    )
    (net (code "81") (name "unconnected-(USB-D+-Pad3)") (class "Default")
      (node (ref "USB") (pin "3") (pinfunction "D+_3") (pintype "passive"))
    )
    (net (code "82") (name "unconnected-(USB-D--Pad2)") (class "Default")
      (node (ref "USB") (pin "2") (pinfunction "D-_2") (pintype "passive"))
    )
    (net (code "83") (name "unconnected-(USB-ID-Pad4)") (class "Default")
      (node (ref "USB") (pin "4") (pinfunction "ID_4") (pintype "passive"))
    )
  )
)
